# SolarRS485-V2_0.net
KiCad netlist of a schematic drawn in EAGLE
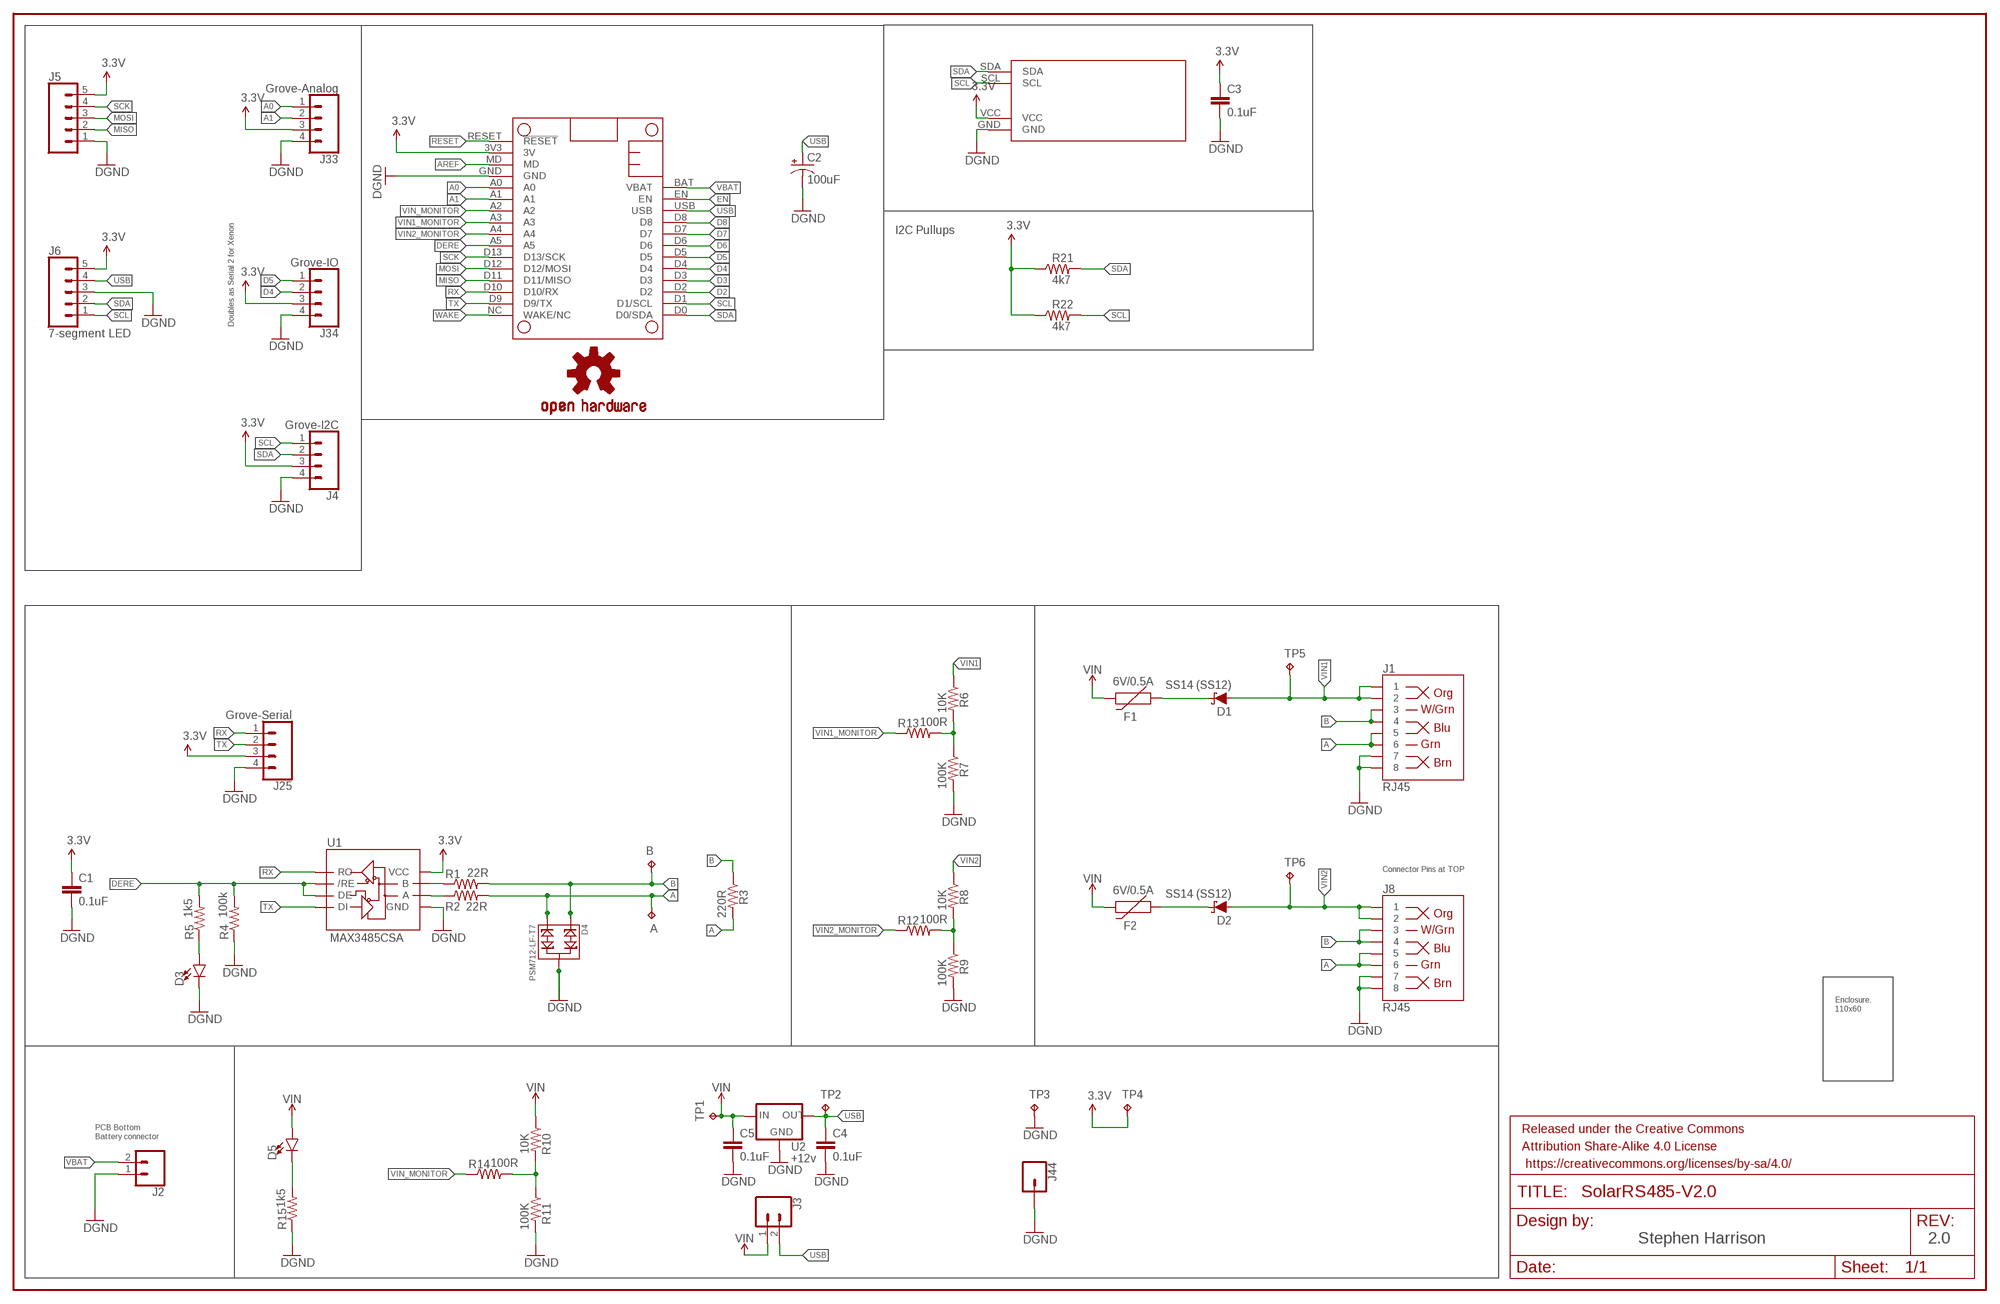
[diagram p0: schematic, sheet 1]

(export (version "E")
  (design (tool "Eeschema 10.0.6"))
  (components
    (comp (ref "A")
      (value "TPTP15R")
      (footprint "eagle-import:TP15R")
      (libsource (lib "eagle-import") (part "TPTP15R"))
    )
    (comp (ref "B")
      (value "TPTP15R")
      (footprint "eagle-import:TP15R")
      (libsource (lib "eagle-import") (part "TPTP15R"))
    )
    (comp (ref "C1")
      (value "0.1uF")
      (footprint "eagle-import:0805")
      (libsource (lib "eagle-import") (part "0.1UF-0805-25V"))
    )
    (comp (ref "C2")
      (value "100uF")
      (footprint "eagle-import:CPOL-RADIAL-2.5MM-6.5MM")
      (libsource (lib "eagle-import") (part "100UF-POLAR-RADIAL-2.5MM-25V-20%"))
    )
    (comp (ref "C3")
      (value "0.1uF")
      (footprint "eagle-import:0805")
      (libsource (lib "eagle-import") (part "0.1UF-0805-25V"))
    )
    (comp (ref "C4")
      (value "0.1uF")
      (footprint "eagle-import:0805")
      (libsource (lib "eagle-import") (part "0.1UF-0805-25V"))
    )
    (comp (ref "C5")
      (value "0.1uF")
      (footprint "eagle-import:0805")
      (libsource (lib "eagle-import") (part "0.1UF-0805-25V"))
    )
    (comp (ref "D1")
      (value "SS14 (SS12)")
      (footprint "eagle-import:SMA-DIODE")
      (libsource (lib "eagle-import") (part "DIODE-SCHOTTKY-SS14"))
    )
    (comp (ref "D2")
      (value "SS14 (SS12)")
      (footprint "eagle-import:SMA-DIODE")
      (libsource (lib "eagle-import") (part "DIODE-SCHOTTKY-SS14"))
    )
    (comp (ref "D3")
      (value "LEDLED-1206-BOTTOM-2.0MM-BLUE")
      (footprint "eagle-import:LED-1206-BOTTOM-2.0MM")
      (libsource (lib "eagle-import") (part "LEDLED-1206-BOTTOM-2.0MM-BLUE"))
    )
    (comp (ref "D4")
      (value "PSM712-LF-T7")
      (footprint "eagle-import:SOT-23")
      (fields (field (name "MPN") "CESD5V0AP"))
      (libsource (lib "eagle-import") (part "SMD-DIODE-TVS-5V-225MW(SOT-23)"))
    )
    (comp (ref "D5")
      (value "LED1206")
      (footprint "eagle-import:LED-1206")
      (libsource (lib "eagle-import") (part "LED1206"))
    )
    (comp (ref "F1")
      (value "6V/0.5A")
      (footprint "eagle-import:1206")
      (libsource (lib "eagle-import") (part "PPTC_HALF-AMP"))
    )
    (comp (ref "F2")
      (value "6V/0.5A")
      (footprint "eagle-import:1206")
      (libsource (lib "eagle-import") (part "PPTC_HALF-AMP"))
    )
    (comp (ref "FRAME2")
      (value "FRAME-LEDGER")
      (footprint "eagle-import:CREATIVE_COMMONS")
      (libsource (lib "eagle-import") (part "FRAME-LEDGER"))
    )
    (comp (ref "J1")
      (value "RJ45")
      (footprint "eagle-import:RJ45-8")
      (libsource (lib "eagle-import") (part "RJ45-8"))
    )
    (comp (ref "J2")
      (value "CONN_02-JST-2MM-SMT")
      (footprint "eagle-import:JST-2-SMD")
      (libsource (lib "eagle-import") (part "CONN_02-JST-2MM-SMT"))
    )
    (comp (ref "J3")
      (value "CONN_02")
      (footprint "eagle-import:1X02")
      (libsource (lib "eagle-import") (part "CONN_02"))
    )
    (comp (ref "J4")
      (value "Grove-I2C")
      (footprint "eagle-import:JST-4-PH-GROVE")
      (libsource (lib "eagle-import") (part "CONN_04GROVE-JST-PH-4-2MM"))
    )
    (comp (ref "J5")
      (value "CONN_05")
      (footprint "eagle-import:1X05")
      (libsource (lib "eagle-import") (part "CONN_05"))
    )
    (comp (ref "J6")
      (value "7-segment LED")
      (footprint "eagle-import:1X05")
      (libsource (lib "eagle-import") (part "CONN_05"))
    )
    (comp (ref "J8")
      (value "RJ45")
      (footprint "eagle-import:RJ45-8")
      (libsource (lib "eagle-import") (part "RJ45-8"))
    )
    (comp (ref "J25")
      (value "Grove-Serial")
      (footprint "eagle-import:JST-4-PH-GROVE")
      (libsource (lib "eagle-import") (part "CONN_04GROVE-JST-PH-4-2MM"))
    )
    (comp (ref "J33")
      (value "Grove-Analog")
      (footprint "eagle-import:JST-4-PH-GROVE")
      (libsource (lib "eagle-import") (part "CONN_04GROVE-JST-PH-4-2MM"))
    )
    (comp (ref "J34")
      (value "Grove-IO")
      (footprint "eagle-import:JST-4-PH-GROVE")
      (libsource (lib "eagle-import") (part "CONN_04GROVE-JST-PH-4-2MM"))
    )
    (comp (ref "J44")
      (value "CONN_01PTH_NO_SILK_YES_STOP")
      (footprint "eagle-import:1X01_NO_SILK")
      (libsource (lib "eagle-import") (part "CONN_01PTH_NO_SILK_YES_STOP"))
    )
    (comp (ref "LOGO1")
      (value "OSHW-LOGOM")
      (footprint "eagle-import:OSHW-LOGO-M")
      (libsource (lib "eagle-import") (part "OSHW-LOGOM"))
    )
    (comp (ref "MS1")
      (value "XENONA")
      (footprint "eagle-import:XENON_BREAKOUT_A")
      (libsource (lib "eagle-import") (part "XENONA"))
    )
    (comp (ref "R1")
      (value "22R")
      (footprint "eagle-import:0805")
      (libsource (lib "eagle-import") (part "RESISTOR0805"))
    )
    (comp (ref "R2")
      (value "22R")
      (footprint "eagle-import:0805")
      (libsource (lib "eagle-import") (part "RESISTOR0805"))
    )
    (comp (ref "R3")
      (value "220R")
      (footprint "eagle-import:0805")
      (libsource (lib "eagle-import") (part "RESISTOR0805"))
    )
    (comp (ref "R4")
      (value "100k")
      (footprint "eagle-import:0805")
      (libsource (lib "eagle-import") (part "RESISTOR0805"))
    )
    (comp (ref "R5")
      (value "1k5")
      (footprint "eagle-import:0805")
      (libsource (lib "eagle-import") (part "RESISTOR0805"))
    )
    (comp (ref "R6")
      (value "10K")
      (footprint "eagle-import:0805")
      (libsource (lib "eagle-import") (part "RESISTOR0805"))
    )
    (comp (ref "R7")
      (value "100K")
      (footprint "eagle-import:0805")
      (libsource (lib "eagle-import") (part "RESISTOR0805"))
    )
    (comp (ref "R8")
      (value "10K")
      (footprint "eagle-import:0805")
      (libsource (lib "eagle-import") (part "RESISTOR0805"))
    )
    (comp (ref "R9")
      (value "100K")
      (footprint "eagle-import:0805")
      (libsource (lib "eagle-import") (part "RESISTOR0805"))
    )
    (comp (ref "R10")
      (value "10K")
      (footprint "eagle-import:0805")
      (libsource (lib "eagle-import") (part "RESISTOR0805"))
    )
    (comp (ref "R11")
      (value "100K")
      (footprint "eagle-import:0805")
      (libsource (lib "eagle-import") (part "RESISTOR0805"))
    )
    (comp (ref "R12")
      (value "100R")
      (footprint "eagle-import:0805")
      (libsource (lib "eagle-import") (part "RESISTOR0805"))
    )
    (comp (ref "R13")
      (value "100R")
      (footprint "eagle-import:0805")
      (libsource (lib "eagle-import") (part "RESISTOR0805"))
    )
    (comp (ref "R14")
      (value "100R")
      (footprint "eagle-import:0805")
      (libsource (lib "eagle-import") (part "RESISTOR0805"))
    )
    (comp (ref "R15")
      (value "1k5")
      (footprint "eagle-import:0805")
      (libsource (lib "eagle-import") (part "RESISTOR0805"))
    )
    (comp (ref "R21")
      (value "4k7")
      (footprint "eagle-import:0805")
      (libsource (lib "eagle-import") (part "RESISTOR0805"))
    )
    (comp (ref "R22")
      (value "4k7")
      (footprint "eagle-import:0805")
      (libsource (lib "eagle-import") (part "RESISTOR0805"))
    )
    (comp (ref "TP1")
      (value "TPTP15R")
      (footprint "eagle-import:TP15R")
      (libsource (lib "eagle-import") (part "TPTP15R"))
    )
    (comp (ref "TP2")
      (value "TPTP15R")
      (footprint "eagle-import:TP15R")
      (libsource (lib "eagle-import") (part "TPTP15R"))
    )
    (comp (ref "TP3")
      (value "TPTP15R")
      (footprint "eagle-import:TP15R")
      (libsource (lib "eagle-import") (part "TPTP15R"))
    )
    (comp (ref "TP4")
      (value "TPTP15R")
      (footprint "eagle-import:TP15R")
      (libsource (lib "eagle-import") (part "TPTP15R"))
    )
    (comp (ref "TP5")
      (value "TPTP15R")
      (footprint "eagle-import:TP15R")
      (libsource (lib "eagle-import") (part "TPTP15R"))
    )
    (comp (ref "TP6")
      (value "TPTP15R")
      (footprint "eagle-import:TP15R")
      (libsource (lib "eagle-import") (part "TPTP15R"))
    )
    (comp (ref "U$1")
      (value "CAMDENBOSS-ENCLOSURE-110X60MAX")
      (footprint "eagle-import:CAMDENBOSS_ENCLOSRE_110X60_WIDE_EXTENDED_3")
      (libsource (lib "eagle-import") (part "CAMDENBOSS-ENCLOSURE-110X60MAX"))
    )
    (comp (ref "U$2")
      (value "DISPLAY0.96_INCH_DISPLAY")
      (footprint "eagle-import:I2C_DISPLAY_0.96_INCH")
      (libsource (lib "eagle-import") (part "DISPLAY0.96_INCH_DISPLAY"))
    )
    (comp (ref "U1")
      (value "MAX3485CSA")
      (footprint "eagle-import:SO08")
      (libsource (lib "eagle-import") (part "RS485SOIC"))
    )
    (comp (ref "U2")
      (value "+12v")
      (footprint "eagle-import:TO-252")
      (libsource (lib "eagle-import") (part "V_REG_78XX7812"))
    )
  )
  (nets
    (net (code "1") (name "3.3V") (class "Default")
      (node (ref "C1") (pin "1") (pinfunction "1_1") (pintype "passive"))
      (node (ref "C3") (pin "1") (pinfunction "1_1") (pintype "passive"))
      (node (ref "J25") (pin "3") (pinfunction "3_3") (pintype "passive"))
      (node (ref "J33") (pin "3") (pinfunction "3_3") (pintype "passive"))
      (node (ref "J34") (pin "3") (pinfunction "3_3") (pintype "passive"))
      (node (ref "J4") (pin "3") (pinfunction "3_3") (pintype "passive"))
      (node (ref "J5") (pin "5") (pinfunction "5_5") (pintype "passive"))
      (node (ref "J6") (pin "5") (pinfunction "5_5") (pintype "passive"))
      (node (ref "MS1") (pin "3V3") (pinfunction "3V_3V3") (pintype "power_in"))
      (node (ref "R21") (pin "1") (pinfunction "1_1") (pintype "passive"))
      (node (ref "R22") (pin "1") (pinfunction "1_1") (pintype "passive"))
      (node (ref "TP4") (pin "TP") (pinfunction "TP_TP") (pintype "input"))
      (node (ref "U$2") (pin "VCC") (pinfunction "VCC_VCC") (pintype "power_in"))
      (node (ref "U1") (pin "8") (pinfunction "VCC_8") (pintype "bidirectional"))
    )
    (net (code "2") (name "A") (class "Default")
      (node (ref "A") (pin "TP") (pinfunction "TP_TP") (pintype "input"))
      (node (ref "D4") (pin "2") (pinfunction "2_2") (pintype "power_in"))
      (node (ref "J1") (pin "5") (pinfunction "5_5") (pintype "bidirectional"))
      (node (ref "J1") (pin "6") (pinfunction "6_6") (pintype "bidirectional"))
      (node (ref "J8") (pin "5") (pinfunction "5_5") (pintype "bidirectional"))
      (node (ref "J8") (pin "6") (pinfunction "6_6") (pintype "bidirectional"))
      (node (ref "R2") (pin "2") (pinfunction "2_2") (pintype "passive"))
      (node (ref "R3") (pin "2") (pinfunction "2_2") (pintype "passive"))
    )
    (net (code "3") (name "A0") (class "Default")
      (node (ref "J33") (pin "1") (pinfunction "1_1") (pintype "passive"))
      (node (ref "MS1") (pin "A0") (pinfunction "A0_A0") (pintype "bidirectional"))
    )
    (net (code "4") (name "A1") (class "Default")
      (node (ref "J33") (pin "2") (pinfunction "2_2") (pintype "passive"))
      (node (ref "MS1") (pin "A1") (pinfunction "A1_A1") (pintype "bidirectional"))
    )
    (net (code "5") (name "AREF") (class "Default")
      (node (ref "MS1") (pin "MD") (pinfunction "MD_MD") (pintype "passive"))
    )
    (net (code "6") (name "B") (class "Default")
      (node (ref "B") (pin "TP") (pinfunction "TP_TP") (pintype "input"))
      (node (ref "D4") (pin "1") (pinfunction "1_1") (pintype "power_in"))
      (node (ref "J1") (pin "3") (pinfunction "3_3") (pintype "bidirectional"))
      (node (ref "J1") (pin "4") (pinfunction "4_4") (pintype "bidirectional"))
      (node (ref "J8") (pin "3") (pinfunction "3_3") (pintype "bidirectional"))
      (node (ref "J8") (pin "4") (pinfunction "4_4") (pintype "bidirectional"))
      (node (ref "R1") (pin "2") (pinfunction "2_2") (pintype "passive"))
      (node (ref "R3") (pin "1") (pinfunction "1_1") (pintype "passive"))
    )
    (net (code "7") (name "D2") (class "Default")
      (node (ref "MS1") (pin "D2") (pinfunction "D2_D2") (pintype "bidirectional"))
    )
    (net (code "8") (name "D3") (class "Default")
      (node (ref "MS1") (pin "D3") (pinfunction "D3_D3") (pintype "bidirectional"))
    )
    (net (code "9") (name "D4") (class "Default")
      (node (ref "J34") (pin "2") (pinfunction "2_2") (pintype "passive"))
      (node (ref "MS1") (pin "D4") (pinfunction "D4_D4") (pintype "bidirectional"))
    )
    (net (code "10") (name "D5") (class "Default")
      (node (ref "J34") (pin "1") (pinfunction "1_1") (pintype "passive"))
      (node (ref "MS1") (pin "D5") (pinfunction "D5_D5") (pintype "bidirectional"))
    )
    (net (code "11") (name "D6") (class "Default")
      (node (ref "MS1") (pin "D6") (pinfunction "D6_D6") (pintype "bidirectional"))
    )
    (net (code "12") (name "D7") (class "Default")
      (node (ref "MS1") (pin "D7") (pinfunction "D7_D7") (pintype "bidirectional"))
    )
    (net (code "13") (name "D8") (class "Default")
      (node (ref "MS1") (pin "D8") (pinfunction "D8_D8") (pintype "bidirectional"))
    )
    (net (code "14") (name "DERE") (class "Default")
      (node (ref "MS1") (pin "A5") (pinfunction "A5_A5") (pintype "bidirectional"))
      (node (ref "R4") (pin "2") (pinfunction "2_2") (pintype "passive"))
      (node (ref "R5") (pin "2") (pinfunction "2_2") (pintype "passive"))
      (node (ref "U1") (pin "2") (pinfunction "/RE_2") (pintype "bidirectional"))
      (node (ref "U1") (pin "3") (pinfunction "DE_3") (pintype "bidirectional"))
    )
    (net (code "15") (name "DGND") (class "Default")
      (node (ref "C1") (pin "2") (pinfunction "2_2") (pintype "passive"))
      (node (ref "C2") (pin "2") (pinfunction "-_2") (pintype "passive"))
      (node (ref "C3") (pin "2") (pinfunction "2_2") (pintype "passive"))
      (node (ref "C4") (pin "2") (pinfunction "2_2") (pintype "passive"))
      (node (ref "C5") (pin "2") (pinfunction "2_2") (pintype "passive"))
      (node (ref "D3") (pin "C") (pinfunction "C_C") (pintype "passive"))
      (node (ref "D4") (pin "3") (pinfunction "3_3") (pintype "bidirectional"))
      (node (ref "J1") (pin "7") (pinfunction "7_7") (pintype "bidirectional"))
      (node (ref "J1") (pin "8") (pinfunction "8_8") (pintype "bidirectional"))
      (node (ref "J2") (pin "1") (pinfunction "2_1") (pintype "passive"))
      (node (ref "J25") (pin "4") (pinfunction "4_4") (pintype "passive"))
      (node (ref "J33") (pin "4") (pinfunction "4_4") (pintype "passive"))
      (node (ref "J34") (pin "4") (pinfunction "4_4") (pintype "passive"))
      (node (ref "J4") (pin "4") (pinfunction "4_4") (pintype "passive"))
      (node (ref "J44") (pin "1") (pinfunction "1_1") (pintype "passive"))
      (node (ref "J5") (pin "1") (pinfunction "1_1") (pintype "passive"))
      (node (ref "J6") (pin "3") (pinfunction "3_3") (pintype "passive"))
      (node (ref "J8") (pin "7") (pinfunction "7_7") (pintype "bidirectional"))
      (node (ref "J8") (pin "8") (pinfunction "8_8") (pintype "bidirectional"))
      (node (ref "MS1") (pin "GND") (pinfunction "GND_GND") (pintype "power_in"))
      (node (ref "R11") (pin "2") (pinfunction "2_2") (pintype "passive"))
      (node (ref "R15") (pin "1") (pinfunction "1_1") (pintype "passive"))
      (node (ref "R4") (pin "1") (pinfunction "1_1") (pintype "passive"))
      (node (ref "R7") (pin "2") (pinfunction "2_2") (pintype "passive"))
      (node (ref "R9") (pin "2") (pinfunction "2_2") (pintype "passive"))
      (node (ref "TP3") (pin "TP") (pinfunction "TP_TP") (pintype "input"))
      (node (ref "U$2") (pin "GND") (pinfunction "GND_GND") (pintype "power_in"))
      (node (ref "U1") (pin "5") (pinfunction "GND_5") (pintype "bidirectional"))
      (node (ref "U2") (pin "3") (pinfunction "GND_3") (pintype "input"))
    )
    (net (code "16") (name "EN") (class "Default")
      (node (ref "MS1") (pin "EN") (pinfunction "EN_EN") (pintype "passive"))
    )
    (net (code "17") (name "MISO") (class "Default")
      (node (ref "J5") (pin "2") (pinfunction "2_2") (pintype "passive"))
      (node (ref "MS1") (pin "D11") (pinfunction "D11/MISO_D11") (pintype "bidirectional"))
    )
    (net (code "18") (name "MOSI") (class "Default")
      (node (ref "J5") (pin "3") (pinfunction "3_3") (pintype "passive"))
      (node (ref "MS1") (pin "D12") (pinfunction "D12/MOSI_D12") (pintype "bidirectional"))
    )
    (net (code "19") (name "Net-(D1-PadC)") (class "Default")
      (node (ref "D1") (pin "C") (pinfunction "C_C") (pintype "passive"))
      (node (ref "F1") (pin "1") (pinfunction "1_1") (pintype "bidirectional"))
    )
    (net (code "20") (name "Net-(D2-PadC)") (class "Default")
      (node (ref "D2") (pin "C") (pinfunction "C_C") (pintype "passive"))
      (node (ref "F2") (pin "1") (pinfunction "1_1") (pintype "bidirectional"))
    )
    (net (code "21") (name "Net-(D3-PadA)") (class "Default")
      (node (ref "D3") (pin "A") (pinfunction "A_A") (pintype "passive"))
      (node (ref "R5") (pin "1") (pinfunction "1_1") (pintype "passive"))
    )
    (net (code "22") (name "Net-(D5-PadC)") (class "Default")
      (node (ref "D5") (pin "C") (pinfunction "C_C") (pintype "passive"))
      (node (ref "R15") (pin "2") (pinfunction "2_2") (pintype "passive"))
    )
    (net (code "23") (name "Net-(R10-Pad2)") (class "Default")
      (node (ref "R10") (pin "2") (pinfunction "2_2") (pintype "passive"))
      (node (ref "R11") (pin "1") (pinfunction "1_1") (pintype "passive"))
      (node (ref "R14") (pin "2") (pinfunction "2_2") (pintype "passive"))
    )
    (net (code "24") (name "Net-(R12-Pad2)") (class "Default")
      (node (ref "R12") (pin "2") (pinfunction "2_2") (pintype "passive"))
      (node (ref "R8") (pin "2") (pinfunction "2_2") (pintype "passive"))
      (node (ref "R9") (pin "1") (pinfunction "1_1") (pintype "passive"))
    )
    (net (code "25") (name "Net-(R13-Pad2)") (class "Default")
      (node (ref "R13") (pin "2") (pinfunction "2_2") (pintype "passive"))
      (node (ref "R6") (pin "2") (pinfunction "2_2") (pintype "passive"))
      (node (ref "R7") (pin "1") (pinfunction "1_1") (pintype "passive"))
    )
    (net (code "26") (name "Net-(U1-A)") (class "Default")
      (node (ref "R2") (pin "1") (pinfunction "1_1") (pintype "passive"))
      (node (ref "U1") (pin "6") (pinfunction "A_6") (pintype "bidirectional"))
    )
    (net (code "27") (name "Net-(U1-B)") (class "Default")
      (node (ref "R1") (pin "1") (pinfunction "1_1") (pintype "passive"))
      (node (ref "U1") (pin "7") (pinfunction "B_7") (pintype "bidirectional"))
    )
    (net (code "28") (name "RESET") (class "Default")
      (node (ref "MS1") (pin "RESET") (pinfunction "~{RESET}_RESET") (pintype "input"))
    )
    (net (code "29") (name "RX") (class "Default")
      (node (ref "J25") (pin "1") (pinfunction "1_1") (pintype "passive"))
      (node (ref "MS1") (pin "D10") (pinfunction "D10/RX_D10") (pintype "bidirectional"))
      (node (ref "U1") (pin "1") (pinfunction "RO_1") (pintype "bidirectional"))
    )
    (net (code "30") (name "SCK") (class "Default")
      (node (ref "J5") (pin "4") (pinfunction "4_4") (pintype "passive"))
      (node (ref "MS1") (pin "D13") (pinfunction "D13/SCK_D13") (pintype "bidirectional"))
    )
    (net (code "31") (name "SCL") (class "Default")
      (node (ref "J4") (pin "1") (pinfunction "1_1") (pintype "passive"))
      (node (ref "J6") (pin "1") (pinfunction "1_1") (pintype "passive"))
      (node (ref "MS1") (pin "D1") (pinfunction "D1/SCL_D1") (pintype "bidirectional"))
      (node (ref "R22") (pin "2") (pinfunction "2_2") (pintype "passive"))
      (node (ref "U$2") (pin "SCL") (pinfunction "SCL_SCL") (pintype "bidirectional"))
    )
    (net (code "32") (name "SDA") (class "Default")
      (node (ref "J4") (pin "2") (pinfunction "2_2") (pintype "passive"))
      (node (ref "J6") (pin "2") (pinfunction "2_2") (pintype "passive"))
      (node (ref "MS1") (pin "D0") (pinfunction "D0/SDA_D0") (pintype "bidirectional"))
      (node (ref "R21") (pin "2") (pinfunction "2_2") (pintype "passive"))
      (node (ref "U$2") (pin "SDA") (pinfunction "SDA_SDA") (pintype "bidirectional"))
    )
    (net (code "33") (name "TX") (class "Default")
      (node (ref "J25") (pin "2") (pinfunction "2_2") (pintype "passive"))
      (node (ref "MS1") (pin "D9") (pinfunction "D9/TX_D9") (pintype "bidirectional"))
      (node (ref "U1") (pin "4") (pinfunction "DI_4") (pintype "bidirectional"))
    )
    (net (code "34") (name "USB") (class "Default")
      (node (ref "C2") (pin "1") (pinfunction "+_1") (pintype "passive"))
      (node (ref "C4") (pin "1") (pinfunction "1_1") (pintype "passive"))
      (node (ref "J3") (pin "2") (pinfunction "2_2") (pintype "passive"))
      (node (ref "J6") (pin "4") (pinfunction "4_4") (pintype "passive"))
      (node (ref "MS1") (pin "USB") (pinfunction "USB_USB") (pintype "power_in"))
      (node (ref "TP2") (pin "TP") (pinfunction "TP_TP") (pintype "input"))
      (node (ref "U2") (pin "2") (pinfunction "OUT_2") (pintype "passive"))
    )
    (net (code "35") (name "VBAT") (class "Default")
      (node (ref "J2") (pin "2") (pinfunction "1_2") (pintype "passive"))
      (node (ref "MS1") (pin "BAT") (pinfunction "VBAT_BAT") (pintype "power_in"))
    )
    (net (code "36") (name "VIN") (class "Default")
      (node (ref "C5") (pin "1") (pinfunction "1_1") (pintype "passive"))
      (node (ref "D5") (pin "A") (pinfunction "A_A") (pintype "passive"))
      (node (ref "F1") (pin "2") (pinfunction "2_2") (pintype "bidirectional"))
      (node (ref "F2") (pin "2") (pinfunction "2_2") (pintype "bidirectional"))
      (node (ref "J3") (pin "1") (pinfunction "1_1") (pintype "passive"))
      (node (ref "R10") (pin "1") (pinfunction "1_1") (pintype "passive"))
      (node (ref "TP1") (pin "TP") (pinfunction "TP_TP") (pintype "input"))
      (node (ref "U2") (pin "1") (pinfunction "IN_1") (pintype "input"))
    )
    (net (code "37") (name "VIN1") (class "Default")
      (node (ref "D1") (pin "A") (pinfunction "A_A") (pintype "passive"))
      (node (ref "J1") (pin "1") (pinfunction "1_1") (pintype "bidirectional"))
      (node (ref "J1") (pin "2") (pinfunction "2_2") (pintype "bidirectional"))
      (node (ref "R6") (pin "1") (pinfunction "1_1") (pintype "passive"))
      (node (ref "TP5") (pin "TP") (pinfunction "TP_TP") (pintype "input"))
    )
    (net (code "38") (name "VIN1_MONITOR") (class "Default")
      (node (ref "MS1") (pin "A3") (pinfunction "A3_A3") (pintype "bidirectional"))
      (node (ref "R13") (pin "1") (pinfunction "1_1") (pintype "passive"))
    )
    (net (code "39") (name "VIN2") (class "Default")
      (node (ref "D2") (pin "A") (pinfunction "A_A") (pintype "passive"))
      (node (ref "J8") (pin "1") (pinfunction "1_1") (pintype "bidirectional"))
      (node (ref "J8") (pin "2") (pinfunction "2_2") (pintype "bidirectional"))
      (node (ref "R8") (pin "1") (pinfunction "1_1") (pintype "passive"))
      (node (ref "TP6") (pin "TP") (pinfunction "TP_TP") (pintype "input"))
    )
    (net (code "40") (name "VIN2_MONITOR") (class "Default")
      (node (ref "MS1") (pin "A4") (pinfunction "A4_A4") (pintype "bidirectional"))
      (node (ref "R12") (pin "1") (pinfunction "1_1") (pintype "passive"))
    )
    (net (code "41") (name "VIN_MONITOR") (class "Default")
      (node (ref "MS1") (pin "A2") (pinfunction "A2_A2") (pintype "bidirectional"))
      (node (ref "R14") (pin "1") (pinfunction "1_1") (pintype "passive"))
    )
    (net (code "42") (name "WAKE") (class "Default")
      (node (ref "MS1") (pin "NC") (pinfunction "WAKE/NC_NC") (pintype "passive"))
    )
  )
)
